# Natsuky.net
KiCad netlist of a schematic drawn in EAGLE
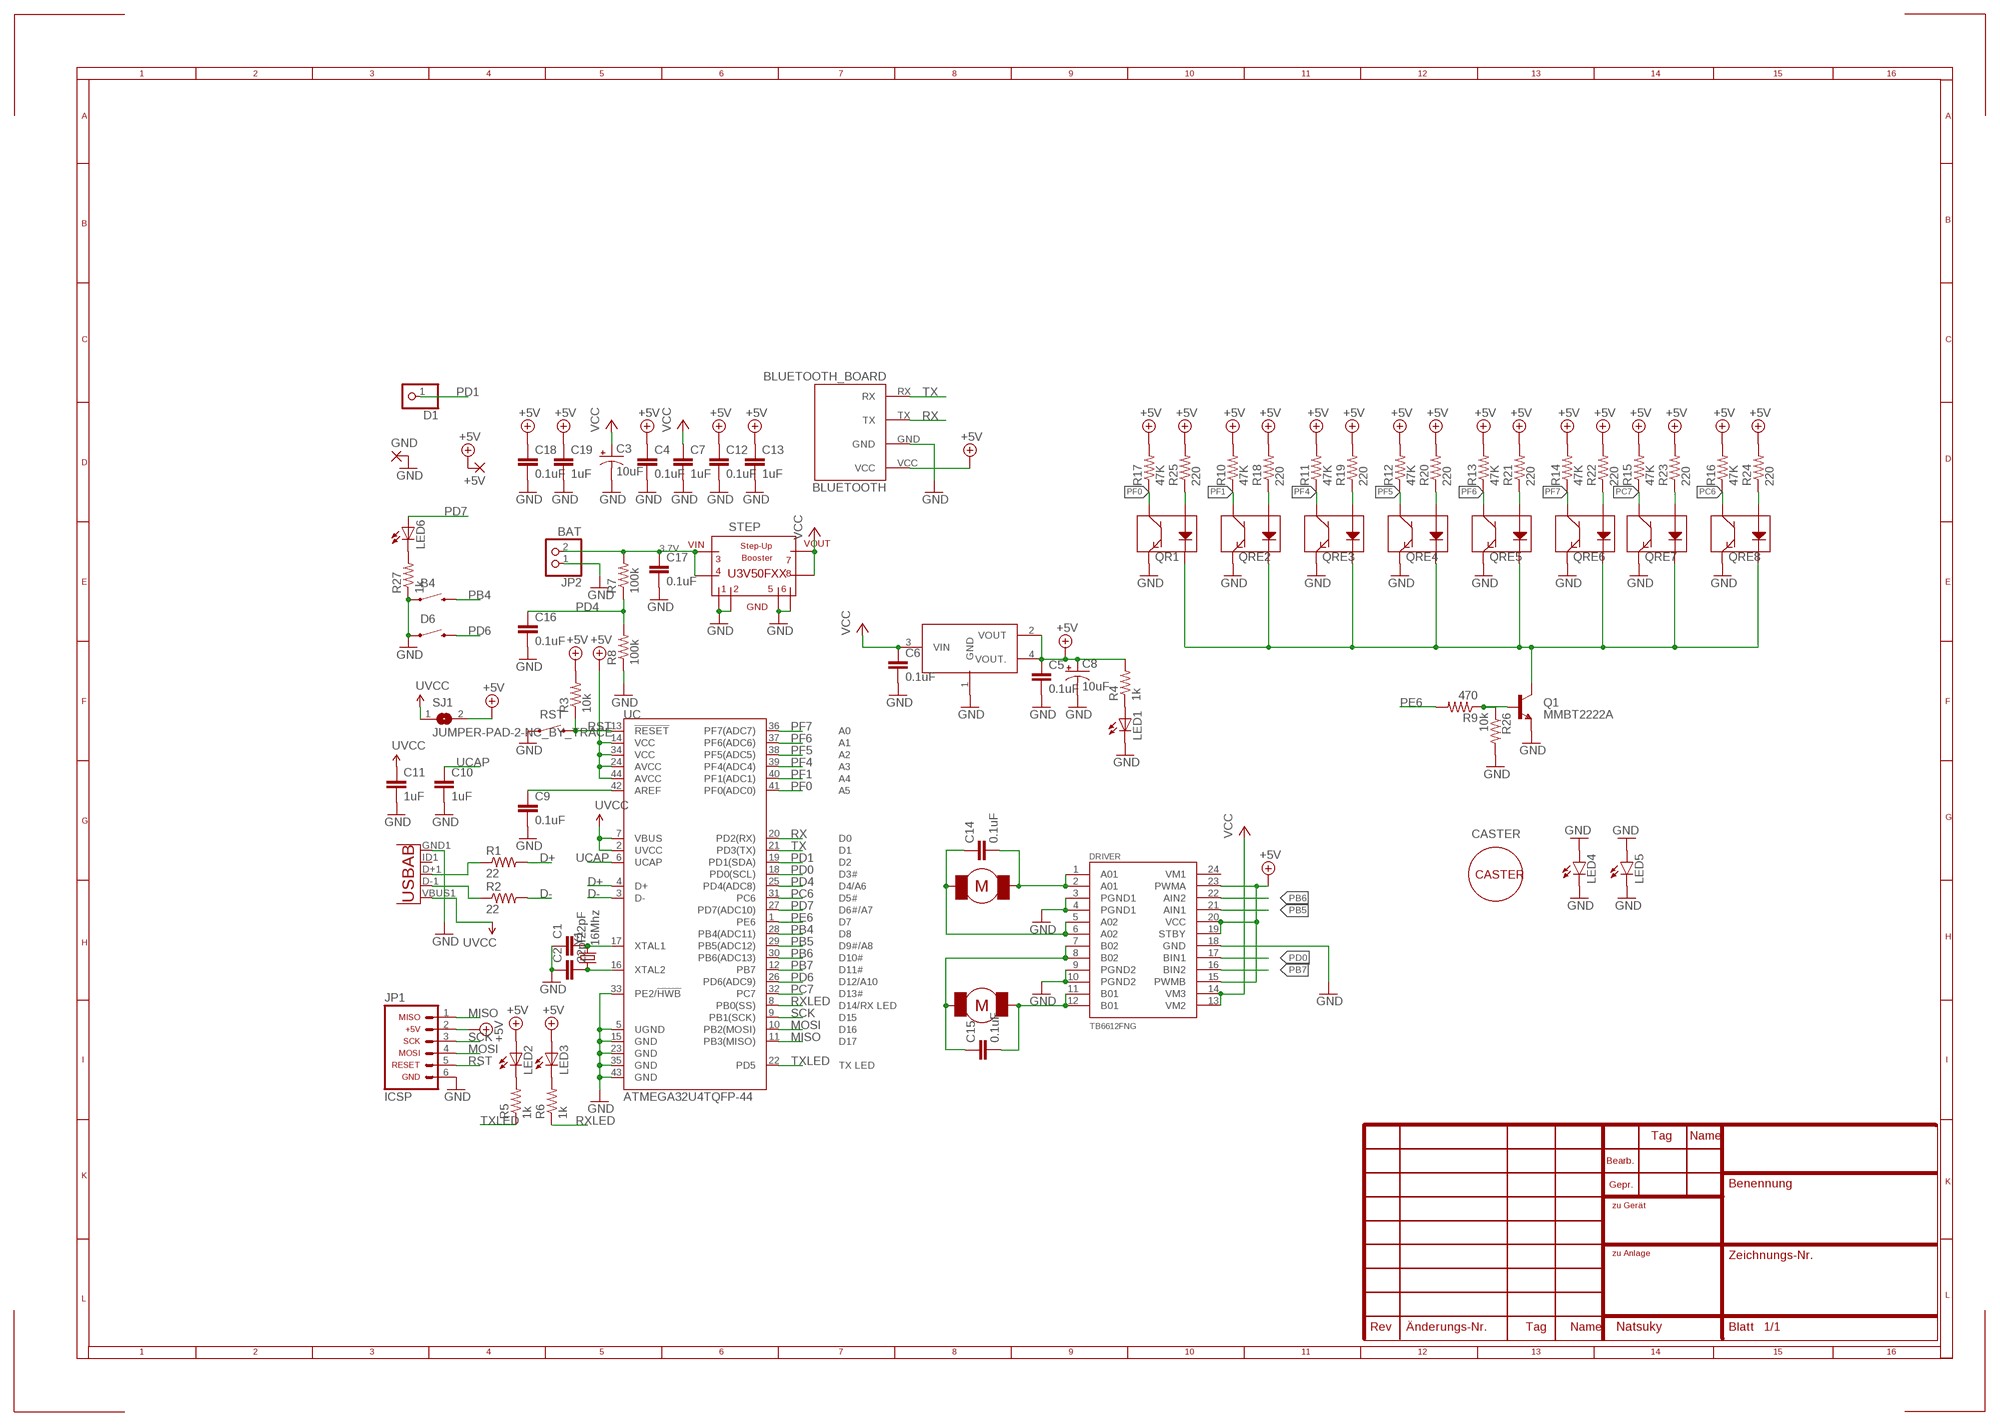
[diagram p0: schematic, sheet 1]

(export (version "E")
  (design (tool "Eeschema 10.0.6"))
  (components
    (comp (ref "+5V")
      (value "SMD2")
      (footprint "eagle-import:SMD1,27-2,54")
      (libsource (lib "eagle-import") (part "SMD2"))
    )
    (comp (ref "B4")
      (value "SWITCH-MOMENTARY-2SMD-1101NE")
      (footprint "eagle-import:TACTILE-SWITCH-1101NE")
      (libsource (lib "eagle-import") (part "SWITCH-MOMENTARY-2SMD-1101NE"))
    )
    (comp (ref "BLUETOOTH")
      (value "BLUETOOTH_BOARD")
      (footprint "eagle-import:BT_BOARD_FOOTPRINT")
      (libsource (lib "eagle-import") (part "BLUETOOTH_BOARD"))
    )
    (comp (ref "C1")
      (value "22pF")
      (footprint "eagle-import:0805")
      (libsource (lib "eagle-import") (part "CAP0805"))
    )
    (comp (ref "C2")
      (value "22pF")
      (footprint "eagle-import:0805")
      (libsource (lib "eagle-import") (part "CAP0805"))
    )
    (comp (ref "C3")
      (value "10uF")
      (footprint "eagle-import:EIA3216")
      (libsource (lib "eagle-import") (part "CAP_POL1206"))
    )
    (comp (ref "C4")
      (value "0.1uF")
      (footprint "eagle-import:0805")
      (libsource (lib "eagle-import") (part "SparkFun-Passives_CAP0805"))
    )
    (comp (ref "C5")
      (value "0.1uF")
      (footprint "eagle-import:0805")
      (libsource (lib "eagle-import") (part "SparkFun-Passives_CAP0805"))
    )
    (comp (ref "C6")
      (value "0.1uF")
      (footprint "eagle-import:0805")
      (libsource (lib "eagle-import") (part "SparkFun-Passives_CAP0805"))
    )
    (comp (ref "C7")
      (value "1uF")
      (footprint "eagle-import:0805")
      (libsource (lib "eagle-import") (part "SparkFun-Passives_CAP0805"))
    )
    (comp (ref "C8")
      (value "10uF")
      (footprint "eagle-import:PANASONIC_D")
      (libsource (lib "eagle-import") (part "CAP_POLD"))
    )
    (comp (ref "C9")
      (value "0.1uF")
      (footprint "eagle-import:0805")
      (libsource (lib "eagle-import") (part "SparkFun-Passives_CAP0805"))
    )
    (comp (ref "C10")
      (value "1uF")
      (footprint "eagle-import:0805")
      (libsource (lib "eagle-import") (part "SparkFun-Passives_CAP0805"))
    )
    (comp (ref "C11")
      (value "1uF")
      (footprint "eagle-import:0805")
      (libsource (lib "eagle-import") (part "SparkFun-Passives_CAP0805"))
    )
    (comp (ref "C12")
      (value "0.1uF")
      (footprint "eagle-import:0805")
      (libsource (lib "eagle-import") (part "SparkFun-Passives_CAP0805"))
    )
    (comp (ref "C13")
      (value "1uF")
      (footprint "eagle-import:0805")
      (libsource (lib "eagle-import") (part "SparkFun-Passives_CAP0805"))
    )
    (comp (ref "C14")
      (value "0.1uF")
      (footprint "eagle-import:0805")
      (libsource (lib "eagle-import") (part "SparkFun-Passives_CAP0805"))
    )
    (comp (ref "C15")
      (value "0.1uF")
      (footprint "eagle-import:0805")
      (libsource (lib "eagle-import") (part "SparkFun-Passives_CAP0805"))
    )
    (comp (ref "C16")
      (value "0.1uF")
      (footprint "eagle-import:0805")
      (libsource (lib "eagle-import") (part "SparkFun-Passives_CAP0805"))
    )
    (comp (ref "C17")
      (value "0.1uF")
      (footprint "eagle-import:0805")
      (libsource (lib "eagle-import") (part "SparkFun-Passives_CAP0805"))
    )
    (comp (ref "C18")
      (value "0.1uF")
      (footprint "eagle-import:0805")
      (libsource (lib "eagle-import") (part "SparkFun-Passives_CAP0805"))
    )
    (comp (ref "C19")
      (value "1uF")
      (footprint "eagle-import:0805")
      (libsource (lib "eagle-import") (part "SparkFun-Passives_CAP0805"))
    )
    (comp (ref "CASTER")
      (value "BALL_CASTER")
      (footprint "eagle-import:BALL_CASTER")
      (libsource (lib "eagle-import") (part "BALL_CASTER"))
    )
    (comp (ref "D1")
      (value "PINHD-1X1")
      (footprint "eagle-import:1X01")
      (libsource (lib "eagle-import") (part "PINHD-1X1"))
    )
    (comp (ref "D6")
      (value "SWITCH-MOMENTARY-2SMD-1101NE")
      (footprint "eagle-import:TACTILE-SWITCH-1101NE")
      (libsource (lib "eagle-import") (part "SWITCH-MOMENTARY-2SMD-1101NE"))
    )
    (comp (ref "DRIVER")
      (value "TB6612FNG")
      (footprint "eagle-import:SSOP24")
      (libsource (lib "eagle-import") (part "TB6612FNG"))
    )
    (comp (ref "GND")
      (value "SMD2")
      (footprint "eagle-import:SMD1,27-2,54")
      (libsource (lib "eagle-import") (part "SMD2"))
    )
    (comp (ref "JP1")
      (value "ICSP")
      (footprint "eagle-import:CONN-2X03")
      (libsource (lib "eagle-import") (part "ARDUINO_CONN-ICSP"))
    )
    (comp (ref "JP2")
      (value "BAT")
      (footprint "eagle-import:1X02")
      (libsource (lib "eagle-import") (part "PINHD-1X2"))
    )
    (comp (ref "LED1")
      (value "LEDCHIPLED_1206")
      (footprint "eagle-import:CHIPLED_1206")
      (libsource (lib "eagle-import") (part "LEDCHIPLED_1206"))
    )
    (comp (ref "LED2")
      (value "LEDCHIPLED_1206")
      (footprint "eagle-import:CHIPLED_1206")
      (libsource (lib "eagle-import") (part "LEDCHIPLED_1206"))
    )
    (comp (ref "LED3")
      (value "LEDCHIPLED_1206")
      (footprint "eagle-import:CHIPLED_1206")
      (libsource (lib "eagle-import") (part "LEDCHIPLED_1206"))
    )
    (comp (ref "LED4")
      (value "LED5MM")
      (footprint "eagle-import:LED5MM")
      (libsource (lib "eagle-import") (part "LED5MM"))
    )
    (comp (ref "LED5")
      (value "LED5MM")
      (footprint "eagle-import:LED5MM")
      (libsource (lib "eagle-import") (part "LED5MM"))
    )
    (comp (ref "LED6")
      (value "LEDCHIPLED_1206")
      (footprint "eagle-import:CHIPLED_1206")
      (libsource (lib "eagle-import") (part "LEDCHIPLED_1206"))
    )
    (comp (ref "M1")
      (value "BRACKET_EXTENDED_WHITE")
      (footprint "eagle-import:WHITE_EXT")
      (libsource (lib "eagle-import") (part "BRACKET_EXTENDED_WHITE"))
    )
    (comp (ref "M2")
      (value "BRACKET_EXTENDED_WHITE")
      (footprint "eagle-import:WHITE_EXT")
      (libsource (lib "eagle-import") (part "BRACKET_EXTENDED_WHITE"))
    )
    (comp (ref "Q1")
      (value "MMBT2222A")
      (footprint "eagle-import:SOT23-3")
      (libsource (lib "eagle-import") (part "TRANSISTOR_NPNMMBT2222A"))
    )
    (comp (ref "QR1")
      (value "QRE1113SMD-W")
      (footprint "eagle-import:QRE1113-W")
      (libsource (lib "eagle-import") (part "QRE1113SMD-W"))
    )
    (comp (ref "QRE2")
      (value "QRE1113SMD-W")
      (footprint "eagle-import:QRE1113-W")
      (libsource (lib "eagle-import") (part "QRE1113SMD-W"))
    )
    (comp (ref "QRE3")
      (value "QRE1113SMD-W")
      (footprint "eagle-import:QRE1113-W")
      (libsource (lib "eagle-import") (part "QRE1113SMD-W"))
    )
    (comp (ref "QRE4")
      (value "QRE1113SMD-W")
      (footprint "eagle-import:QRE1113-W")
      (libsource (lib "eagle-import") (part "QRE1113SMD-W"))
    )
    (comp (ref "QRE5")
      (value "QRE1113SMD-W")
      (footprint "eagle-import:QRE1113-W")
      (libsource (lib "eagle-import") (part "QRE1113SMD-W"))
    )
    (comp (ref "QRE6")
      (value "QRE1113SMD-W")
      (footprint "eagle-import:QRE1113-W")
      (libsource (lib "eagle-import") (part "QRE1113SMD-W"))
    )
    (comp (ref "QRE7")
      (value "QRE1113SMD-W")
      (footprint "eagle-import:QRE1113-W")
      (libsource (lib "eagle-import") (part "QRE1113SMD-W"))
    )
    (comp (ref "QRE8")
      (value "QRE1113SMD-W")
      (footprint "eagle-import:QRE1113-W")
      (libsource (lib "eagle-import") (part "QRE1113SMD-W"))
    )
    (comp (ref "R1")
      (value "22")
      (footprint "eagle-import:0805")
      (libsource (lib "eagle-import") (part "RESISTOR0805-RES"))
    )
    (comp (ref "R2")
      (value "22")
      (footprint "eagle-import:0805")
      (libsource (lib "eagle-import") (part "RESISTOR0805-RES"))
    )
    (comp (ref "R3")
      (value "10k")
      (footprint "eagle-import:0805")
      (libsource (lib "eagle-import") (part "RESISTOR0805-RES"))
    )
    (comp (ref "R4")
      (value "1k")
      (footprint "eagle-import:0805")
      (libsource (lib "eagle-import") (part "RESISTOR0805-RES"))
    )
    (comp (ref "R5")
      (value "1k")
      (footprint "eagle-import:0805")
      (libsource (lib "eagle-import") (part "RESISTOR0805-RES"))
    )
    (comp (ref "R6")
      (value "1k")
      (footprint "eagle-import:0805")
      (libsource (lib "eagle-import") (part "RESISTOR0805-RES"))
    )
    (comp (ref "R7")
      (value "100k")
      (footprint "eagle-import:0805")
      (libsource (lib "eagle-import") (part "RESISTOR0805-RES"))
    )
    (comp (ref "R8")
      (value "100k")
      (footprint "eagle-import:0805")
      (libsource (lib "eagle-import") (part "RESISTOR0805-RES"))
    )
    (comp (ref "R9")
      (value "470")
      (footprint "eagle-import:0805")
      (libsource (lib "eagle-import") (part "RESISTOR0805-RES"))
    )
    (comp (ref "R10")
      (value "47K")
      (footprint "eagle-import:0805")
      (libsource (lib "eagle-import") (part "RESISTOR0805-RES"))
    )
    (comp (ref "R11")
      (value "47K")
      (footprint "eagle-import:0805")
      (libsource (lib "eagle-import") (part "RESISTOR0805-RES"))
    )
    (comp (ref "R12")
      (value "47K")
      (footprint "eagle-import:0805")
      (libsource (lib "eagle-import") (part "RESISTOR0805-RES"))
    )
    (comp (ref "R13")
      (value "47K")
      (footprint "eagle-import:0805")
      (libsource (lib "eagle-import") (part "RESISTOR0805-RES"))
    )
    (comp (ref "R14")
      (value "47K")
      (footprint "eagle-import:0805")
      (libsource (lib "eagle-import") (part "RESISTOR0805-RES"))
    )
    (comp (ref "R15")
      (value "47K")
      (footprint "eagle-import:0805")
      (libsource (lib "eagle-import") (part "RESISTOR0805-RES"))
    )
    (comp (ref "R16")
      (value "47K")
      (footprint "eagle-import:0805")
      (libsource (lib "eagle-import") (part "RESISTOR0805-RES"))
    )
    (comp (ref "R17")
      (value "47K")
      (footprint "eagle-import:0805")
      (libsource (lib "eagle-import") (part "RESISTOR0805-RES"))
    )
    (comp (ref "R18")
      (value "220")
      (footprint "eagle-import:0805")
      (libsource (lib "eagle-import") (part "RESISTOR0805-RES"))
    )
    (comp (ref "R19")
      (value "220")
      (footprint "eagle-import:0805")
      (libsource (lib "eagle-import") (part "RESISTOR0805-RES"))
    )
    (comp (ref "R20")
      (value "220")
      (footprint "eagle-import:0805")
      (libsource (lib "eagle-import") (part "RESISTOR0805-RES"))
    )
    (comp (ref "R21")
      (value "220")
      (footprint "eagle-import:0805")
      (libsource (lib "eagle-import") (part "RESISTOR0805-RES"))
    )
    (comp (ref "R22")
      (value "220")
      (footprint "eagle-import:0805")
      (libsource (lib "eagle-import") (part "RESISTOR0805-RES"))
    )
    (comp (ref "R23")
      (value "220")
      (footprint "eagle-import:0805")
      (libsource (lib "eagle-import") (part "RESISTOR0805-RES"))
    )
    (comp (ref "R24")
      (value "220")
      (footprint "eagle-import:0805")
      (libsource (lib "eagle-import") (part "RESISTOR0805-RES"))
    )
    (comp (ref "R25")
      (value "220")
      (footprint "eagle-import:0805")
      (libsource (lib "eagle-import") (part "RESISTOR0805-RES"))
    )
    (comp (ref "R26")
      (value "10k")
      (footprint "eagle-import:0805")
      (libsource (lib "eagle-import") (part "RESISTOR0805-RES"))
    )
    (comp (ref "R27")
      (value "1k")
      (footprint "eagle-import:0805")
      (libsource (lib "eagle-import") (part "RESISTOR0805-RES"))
    )
    (comp (ref "REG")
      (value "LD1117S50TR")
      (footprint "eagle-import:SOT223")
      (libsource (lib "eagle-import") (part "LD1117S50TR"))
    )
    (comp (ref "RST")
      (value "SWITCH-MOMENTARY-2SMD-1101NE")
      (footprint "eagle-import:TACTILE-SWITCH-1101NE")
      (libsource (lib "eagle-import") (part "SWITCH-MOMENTARY-2SMD-1101NE"))
    )
    (comp (ref "SJ1")
      (value "JUMPER-PAD-2-NC_BY_TRACE")
      (footprint "eagle-import:SJ")
      (libsource (lib "eagle-import") (part "SJ"))
    )
    (comp (ref "STEP")
      (value "STEP-UP")
      (footprint "eagle-import:U3V50F12")
      (libsource (lib "eagle-import") (part "STEP-UP"))
    )
    (comp (ref "UC")
      (value "ATMEGA32U4TQFP-44")
      (footprint "eagle-import:TQFP44")
      (libsource (lib "eagle-import") (part "ATMEGA32U4TQFP-44"))
    )
    (comp (ref "X1")
      (value "usb")
      (footprint "eagle-import:USB-AB-MICRO-SMD-V03-IN&OUT")
      (libsource (lib "eagle-import") (part "USB-ABIN&OUT"))
    )
    (comp (ref "Y1")
      (value "16Mhz")
      (footprint "eagle-import:HC49US")
      (libsource (lib "eagle-import") (part "CRYSTALHC49US"))
    )
  )
  (nets
    (net (code "1") (name "+5V") (class "Default")
      (node (ref "+5V") (pin "1") (pinfunction "P_1") (pintype "passive"))
      (node (ref "BLUETOOTH") (pin "VCC") (pinfunction "VCC_VCC") (pintype "bidirectional"))
      (node (ref "C12") (pin "1") (pinfunction "1_1") (pintype "passive"))
      (node (ref "C13") (pin "1") (pinfunction "1_1") (pintype "passive"))
      (node (ref "C18") (pin "1") (pinfunction "1_1") (pintype "passive"))
      (node (ref "C19") (pin "1") (pinfunction "1_1") (pintype "passive"))
      (node (ref "C4") (pin "1") (pinfunction "1_1") (pintype "passive"))
      (node (ref "C5") (pin "1") (pinfunction "1_1") (pintype "passive"))
      (node (ref "C8") (pin "+") (pinfunction "+_+") (pintype "passive"))
      (node (ref "DRIVER") (pin "15") (pinfunction "PWMB_15") (pintype "bidirectional"))
      (node (ref "DRIVER") (pin "19") (pinfunction "STBY_19") (pintype "bidirectional"))
      (node (ref "DRIVER") (pin "20") (pinfunction "VCC_20") (pintype "bidirectional"))
      (node (ref "DRIVER") (pin "23") (pinfunction "PWMA_23") (pintype "bidirectional"))
      (node (ref "JP1") (pin "2") (pinfunction "2_2") (pintype "passive"))
      (node (ref "LED2") (pin "A") (pinfunction "A_A") (pintype "passive"))
      (node (ref "LED3") (pin "A") (pinfunction "A_A") (pintype "passive"))
      (node (ref "R10") (pin "2") (pinfunction "2_2") (pintype "passive"))
      (node (ref "R11") (pin "2") (pinfunction "2_2") (pintype "passive"))
      (node (ref "R12") (pin "2") (pinfunction "2_2") (pintype "passive"))
      (node (ref "R13") (pin "2") (pinfunction "2_2") (pintype "passive"))
      (node (ref "R14") (pin "2") (pinfunction "2_2") (pintype "passive"))
      (node (ref "R15") (pin "2") (pinfunction "2_2") (pintype "passive"))
      (node (ref "R16") (pin "2") (pinfunction "2_2") (pintype "passive"))
      (node (ref "R17") (pin "2") (pinfunction "2_2") (pintype "passive"))
      (node (ref "R18") (pin "2") (pinfunction "2_2") (pintype "passive"))
      (node (ref "R19") (pin "2") (pinfunction "2_2") (pintype "passive"))
      (node (ref "R20") (pin "2") (pinfunction "2_2") (pintype "passive"))
      (node (ref "R21") (pin "2") (pinfunction "2_2") (pintype "passive"))
      (node (ref "R22") (pin "2") (pinfunction "2_2") (pintype "passive"))
      (node (ref "R23") (pin "2") (pinfunction "2_2") (pintype "passive"))
      (node (ref "R24") (pin "2") (pinfunction "2_2") (pintype "passive"))
      (node (ref "R25") (pin "2") (pinfunction "2_2") (pintype "passive"))
      (node (ref "R3") (pin "2") (pinfunction "2_2") (pintype "passive"))
      (node (ref "R4") (pin "2") (pinfunction "2_2") (pintype "passive"))
      (node (ref "REG") (pin "2") (pinfunction "VOUT_2") (pintype "bidirectional"))
      (node (ref "REG") (pin "4") (pinfunction "VOUT._4") (pintype "bidirectional"))
      (node (ref "SJ1") (pin "2") (pinfunction "2_2") (pintype "passive"))
      (node (ref "UC") (pin "14") (pinfunction "VCC_14") (pintype "bidirectional"))
      (node (ref "UC") (pin "24") (pinfunction "AVCC_24") (pintype "bidirectional"))
      (node (ref "UC") (pin "34") (pinfunction "VCC_34") (pintype "bidirectional"))
      (node (ref "UC") (pin "44") (pinfunction "AVCC_44") (pintype "bidirectional"))
    )
    (net (code "2") (name "/3.7V") (class "Default")
      (node (ref "C17") (pin "1") (pinfunction "1_1") (pintype "passive"))
      (node (ref "JP2") (pin "2") (pinfunction "2_2") (pintype "passive"))
      (node (ref "R7") (pin "2") (pinfunction "2_2") (pintype "passive"))
      (node (ref "STEP") (pin "VIN") (pinfunction "VIN_VIN") (pintype "bidirectional"))
      (node (ref "STEP") (pin "VIN_4") (pinfunction "VIN4_VIN_4") (pintype "bidirectional"))
    )
    (net (code "3") (name "/D+") (class "Default")
      (node (ref "R1") (pin "2") (pinfunction "2_2") (pintype "passive"))
      (node (ref "UC") (pin "4") (pinfunction "D+_4") (pintype "bidirectional"))
    )
    (net (code "4") (name "/D-") (class "Default")
      (node (ref "R2") (pin "2") (pinfunction "2_2") (pintype "passive"))
      (node (ref "UC") (pin "3") (pinfunction "D-_3") (pintype "bidirectional"))
    )
    (net (code "5") (name "/MISO") (class "Default")
      (node (ref "JP1") (pin "1") (pinfunction "1_1") (pintype "passive"))
      (node (ref "UC") (pin "11") (pinfunction "PB3(MISO)_11") (pintype "bidirectional"))
    )
    (net (code "6") (name "/MOSI") (class "Default")
      (node (ref "JP1") (pin "4") (pinfunction "4_4") (pintype "passive"))
      (node (ref "UC") (pin "10") (pinfunction "PB2(MOSI)_10") (pintype "bidirectional"))
    )
    (net (code "7") (name "/PB4") (class "Default")
      (node (ref "B4") (pin "2") (pinfunction "2_2") (pintype "passive"))
      (node (ref "UC") (pin "28") (pinfunction "PB4(ADC11)_28") (pintype "bidirectional"))
    )
    (net (code "8") (name "/PD1") (class "Default")
      (node (ref "D1") (pin "1") (pinfunction "1_1") (pintype "passive"))
      (node (ref "UC") (pin "19") (pinfunction "PD1(SDA)_19") (pintype "bidirectional"))
    )
    (net (code "9") (name "/PD4") (class "Default")
      (node (ref "C16") (pin "1") (pinfunction "1_1") (pintype "passive"))
      (node (ref "R7") (pin "1") (pinfunction "1_1") (pintype "passive"))
      (node (ref "R8") (pin "2") (pinfunction "2_2") (pintype "passive"))
      (node (ref "UC") (pin "25") (pinfunction "PD4(ADC8)_25") (pintype "bidirectional"))
    )
    (net (code "10") (name "/PD6") (class "Default")
      (node (ref "D6") (pin "2") (pinfunction "2_2") (pintype "passive"))
      (node (ref "UC") (pin "26") (pinfunction "PD6(ADC9)_26") (pintype "bidirectional"))
    )
    (net (code "11") (name "/PD7") (class "Default")
      (node (ref "LED6") (pin "A") (pinfunction "A_A") (pintype "passive"))
      (node (ref "UC") (pin "27") (pinfunction "PD7(ADC10)_27") (pintype "bidirectional"))
    )
    (net (code "12") (name "/PE6") (class "Default")
      (node (ref "R9") (pin "2") (pinfunction "2_2") (pintype "passive"))
      (node (ref "UC") (pin "1") (pinfunction "PE6_1") (pintype "bidirectional"))
    )
    (net (code "13") (name "/RST") (class "Default")
      (node (ref "JP1") (pin "5") (pinfunction "5_5") (pintype "passive"))
      (node (ref "R3") (pin "1") (pinfunction "1_1") (pintype "passive"))
      (node (ref "RST") (pin "2") (pinfunction "2_2") (pintype "passive"))
      (node (ref "UC") (pin "13") (pinfunction "~{RESET}_13") (pintype "bidirectional"))
    )
    (net (code "14") (name "/RX") (class "Default")
      (node (ref "BLUETOOTH") (pin "TX") (pinfunction "TX_TX") (pintype "bidirectional"))
      (node (ref "UC") (pin "20") (pinfunction "PD2(RX)_20") (pintype "bidirectional"))
    )
    (net (code "15") (name "/RXLED") (class "Default")
      (node (ref "R6") (pin "1") (pinfunction "1_1") (pintype "passive"))
      (node (ref "UC") (pin "8") (pinfunction "PB0(SS)_8") (pintype "bidirectional"))
    )
    (net (code "16") (name "/SCK") (class "Default")
      (node (ref "JP1") (pin "3") (pinfunction "3_3") (pintype "passive"))
      (node (ref "UC") (pin "9") (pinfunction "PB1(SCK)_9") (pintype "bidirectional"))
    )
    (net (code "17") (name "/TX") (class "Default")
      (node (ref "BLUETOOTH") (pin "RX") (pinfunction "RX_RX") (pintype "bidirectional"))
      (node (ref "UC") (pin "21") (pinfunction "PD3(TX)_21") (pintype "bidirectional"))
    )
    (net (code "18") (name "/TXLED") (class "Default")
      (node (ref "R5") (pin "1") (pinfunction "1_1") (pintype "passive"))
      (node (ref "UC") (pin "22") (pinfunction "PD5_22") (pintype "bidirectional"))
    )
    (net (code "19") (name "/UCAP") (class "Default")
      (node (ref "C10") (pin "1") (pinfunction "1_1") (pintype "passive"))
      (node (ref "UC") (pin "6") (pinfunction "UCAP_6") (pintype "bidirectional"))
    )
    (net (code "20") (name "GND") (class "Default")
      (node (ref "B4") (pin "1") (pinfunction "1_1") (pintype "passive"))
      (node (ref "BLUETOOTH") (pin "GND") (pinfunction "GND_GND") (pintype "bidirectional"))
      (node (ref "C1") (pin "1") (pinfunction "1_1") (pintype "passive"))
      (node (ref "C10") (pin "2") (pinfunction "2_2") (pintype "passive"))
      (node (ref "C11") (pin "2") (pinfunction "2_2") (pintype "passive"))
      (node (ref "C12") (pin "2") (pinfunction "2_2") (pintype "passive"))
      (node (ref "C13") (pin "2") (pinfunction "2_2") (pintype "passive"))
      (node (ref "C16") (pin "2") (pinfunction "2_2") (pintype "passive"))
      (node (ref "C17") (pin "2") (pinfunction "2_2") (pintype "passive"))
      (node (ref "C18") (pin "2") (pinfunction "2_2") (pintype "passive"))
      (node (ref "C19") (pin "2") (pinfunction "2_2") (pintype "passive"))
      (node (ref "C2") (pin "1") (pinfunction "1_1") (pintype "passive"))
      (node (ref "C3") (pin "C") (pinfunction "-_C") (pintype "passive"))
      (node (ref "C4") (pin "2") (pinfunction "2_2") (pintype "passive"))
      (node (ref "C5") (pin "2") (pinfunction "2_2") (pintype "passive"))
      (node (ref "C6") (pin "2") (pinfunction "2_2") (pintype "passive"))
      (node (ref "C7") (pin "2") (pinfunction "2_2") (pintype "passive"))
      (node (ref "C8") (pin "-") (pinfunction "-_-") (pintype "passive"))
      (node (ref "C9") (pin "2") (pinfunction "2_2") (pintype "passive"))
      (node (ref "D6") (pin "1") (pinfunction "1_1") (pintype "passive"))
      (node (ref "DRIVER") (pin "10") (pinfunction "PGND2_10") (pintype "bidirectional"))
      (node (ref "DRIVER") (pin "18") (pinfunction "GND_18") (pintype "bidirectional"))
      (node (ref "DRIVER") (pin "3") (pinfunction "PGND1_3") (pintype "bidirectional"))
      (node (ref "DRIVER") (pin "4") (pinfunction "PGND1_4") (pintype "bidirectional"))
      (node (ref "DRIVER") (pin "9") (pinfunction "PGND2_9") (pintype "bidirectional"))
      (node (ref "GND") (pin "1") (pinfunction "P_1") (pintype "passive"))
      (node (ref "JP1") (pin "6") (pinfunction "6_6") (pintype "passive"))
      (node (ref "JP2") (pin "1") (pinfunction "1_1") (pintype "passive"))
      (node (ref "LED1") (pin "C") (pinfunction "C_C") (pintype "passive"))
      (node (ref "LED4") (pin "A") (pinfunction "A_A") (pintype "passive"))
      (node (ref "LED4") (pin "K") (pinfunction "C_K") (pintype "passive"))
      (node (ref "LED5") (pin "A") (pinfunction "A_A") (pintype "passive"))
      (node (ref "LED5") (pin "K") (pinfunction "C_K") (pintype "passive"))
      (node (ref "Q1") (pin "2") (pinfunction "E_2") (pintype "passive"))
      (node (ref "QR1") (pin "4") (pinfunction "E_4") (pintype "bidirectional"))
      (node (ref "QRE2") (pin "4") (pinfunction "E_4") (pintype "bidirectional"))
      (node (ref "QRE3") (pin "4") (pinfunction "E_4") (pintype "bidirectional"))
      (node (ref "QRE4") (pin "4") (pinfunction "E_4") (pintype "bidirectional"))
      (node (ref "QRE5") (pin "4") (pinfunction "E_4") (pintype "bidirectional"))
      (node (ref "QRE6") (pin "4") (pinfunction "E_4") (pintype "bidirectional"))
      (node (ref "QRE7") (pin "4") (pinfunction "E_4") (pintype "bidirectional"))
      (node (ref "QRE8") (pin "4") (pinfunction "E_4") (pintype "bidirectional"))
      (node (ref "R26") (pin "2") (pinfunction "2_2") (pintype "passive"))
      (node (ref "R27") (pin "1") (pinfunction "1_1") (pintype "passive"))
      (node (ref "R8") (pin "1") (pinfunction "1_1") (pintype "passive"))
      (node (ref "REG") (pin "1") (pinfunction "GND_1") (pintype "bidirectional"))
      (node (ref "RST") (pin "1") (pinfunction "1_1") (pintype "passive"))
      (node (ref "STEP") (pin "GND_OUT") (pinfunction "GND_VOUT_GND_OUT") (pintype "bidirectional"))
      (node (ref "STEP") (pin "GND_OUT_1") (pinfunction "GND_OUT1_GND_OUT_1") (pintype "bidirectional"))
      (node (ref "STEP") (pin "GND_VIN") (pinfunction "GND_VIN_GND_VIN") (pintype "bidirectional"))
      (node (ref "STEP") (pin "GND_VIN_1") (pinfunction "GND_VIN1_GND_VIN_1") (pintype "bidirectional"))
      (node (ref "UC") (pin "15") (pinfunction "GND_15") (pintype "bidirectional"))
      (node (ref "UC") (pin "23") (pinfunction "GND_23") (pintype "bidirectional"))
      (node (ref "UC") (pin "33") (pinfunction "PE2/~{HWB}_33") (pintype "bidirectional"))
      (node (ref "UC") (pin "35") (pinfunction "GND_35") (pintype "bidirectional"))
      (node (ref "UC") (pin "43") (pinfunction "GND_43") (pintype "bidirectional"))
      (node (ref "UC") (pin "5") (pinfunction "UGND_5") (pintype "bidirectional"))
      (node (ref "X1") (pin "GND1") (pinfunction "GND_GND1") (pintype "bidirectional"))
    )
    (net (code "21") (name "Net-(C14-Pad1)") (class "Default")
      (node (ref "C14") (pin "1") (pinfunction "1_1") (pintype "passive"))
      (node (ref "DRIVER") (pin "5") (pinfunction "A02_5") (pintype "bidirectional"))
      (node (ref "DRIVER") (pin "6") (pinfunction "A02_6") (pintype "bidirectional"))
      (node (ref "M2") (pin "M2") (pinfunction "M2_M2") (pintype "bidirectional"))
    )
    (net (code "22") (name "Net-(C14-Pad2)") (class "Default")
      (node (ref "C14") (pin "2") (pinfunction "2_2") (pintype "passive"))
      (node (ref "DRIVER") (pin "1") (pinfunction "A01_1") (pintype "bidirectional"))
      (node (ref "DRIVER") (pin "2") (pinfunction "A01_2") (pintype "bidirectional"))
      (node (ref "M2") (pin "M1") (pinfunction "M1_M1") (pintype "bidirectional"))
    )
    (net (code "23") (name "Net-(C15-Pad1)") (class "Default")
      (node (ref "C15") (pin "1") (pinfunction "1_1") (pintype "passive"))
      (node (ref "DRIVER") (pin "7") (pinfunction "B02_7") (pintype "bidirectional"))
      (node (ref "DRIVER") (pin "8") (pinfunction "B02_8") (pintype "bidirectional"))
      (node (ref "M1") (pin "M1") (pinfunction "M1_M1") (pintype "bidirectional"))
    )
    (net (code "24") (name "Net-(C15-Pad2)") (class "Default")
      (node (ref "C15") (pin "2") (pinfunction "2_2") (pintype "passive"))
      (node (ref "DRIVER") (pin "11") (pinfunction "B01_11") (pintype "bidirectional"))
      (node (ref "DRIVER") (pin "12") (pinfunction "B01_12") (pintype "bidirectional"))
      (node (ref "M1") (pin "M2") (pinfunction "M2_M2") (pintype "bidirectional"))
    )
    (net (code "25") (name "Net-(LED1-PadA)") (class "Default")
      (node (ref "LED1") (pin "A") (pinfunction "A_A") (pintype "passive"))
      (node (ref "R4") (pin "1") (pinfunction "1_1") (pintype "passive"))
    )
    (net (code "26") (name "Net-(LED2-PadC)") (class "Default")
      (node (ref "LED2") (pin "C") (pinfunction "C_C") (pintype "passive"))
      (node (ref "R5") (pin "2") (pinfunction "2_2") (pintype "passive"))
    )
    (net (code "27") (name "Net-(LED3-PadC)") (class "Default")
      (node (ref "LED3") (pin "C") (pinfunction "C_C") (pintype "passive"))
      (node (ref "R6") (pin "2") (pinfunction "2_2") (pintype "passive"))
    )
    (net (code "28") (name "Net-(LED6-PadC)") (class "Default")
      (node (ref "LED6") (pin "C") (pinfunction "C_C") (pintype "passive"))
      (node (ref "R27") (pin "2") (pinfunction "2_2") (pintype "passive"))
    )
    (net (code "29") (name "Net-(Q1-B)") (class "Default")
      (node (ref "Q1") (pin "1") (pinfunction "B_1") (pintype "passive"))
      (node (ref "R26") (pin "1") (pinfunction "1_1") (pintype "passive"))
      (node (ref "R9") (pin "1") (pinfunction "1_1") (pintype "passive"))
    )
    (net (code "30") (name "Net-(Q1-C)") (class "Default")
      (node (ref "Q1") (pin "3") (pinfunction "C_3") (pintype "passive"))
      (node (ref "QR1") (pin "2") (pinfunction "K_2") (pintype "bidirectional"))
      (node (ref "QRE2") (pin "2") (pinfunction "K_2") (pintype "bidirectional"))
      (node (ref "QRE3") (pin "2") (pinfunction "K_2") (pintype "bidirectional"))
      (node (ref "QRE4") (pin "2") (pinfunction "K_2") (pintype "bidirectional"))
      (node (ref "QRE5") (pin "2") (pinfunction "K_2") (pintype "bidirectional"))
      (node (ref "QRE6") (pin "2") (pinfunction "K_2") (pintype "bidirectional"))
      (node (ref "QRE7") (pin "2") (pinfunction "K_2") (pintype "bidirectional"))
      (node (ref "QRE8") (pin "2") (pinfunction "K_2") (pintype "bidirectional"))
    )
    (net (code "31") (name "Net-(QR1-A)") (class "Default")
      (node (ref "QR1") (pin "1") (pinfunction "A_1") (pintype "bidirectional"))
      (node (ref "R25") (pin "1") (pinfunction "1_1") (pintype "passive"))
    )
    (net (code "32") (name "Net-(QRE2-A)") (class "Default")
      (node (ref "QRE2") (pin "1") (pinfunction "A_1") (pintype "bidirectional"))
      (node (ref "R18") (pin "1") (pinfunction "1_1") (pintype "passive"))
    )
    (net (code "33") (name "Net-(QRE3-A)") (class "Default")
      (node (ref "QRE3") (pin "1") (pinfunction "A_1") (pintype "bidirectional"))
      (node (ref "R19") (pin "1") (pinfunction "1_1") (pintype "passive"))
    )
    (net (code "34") (name "Net-(QRE4-A)") (class "Default")
      (node (ref "QRE4") (pin "1") (pinfunction "A_1") (pintype "bidirectional"))
      (node (ref "R20") (pin "1") (pinfunction "1_1") (pintype "passive"))
    )
    (net (code "35") (name "Net-(QRE5-A)") (class "Default")
      (node (ref "QRE5") (pin "1") (pinfunction "A_1") (pintype "bidirectional"))
      (node (ref "R21") (pin "1") (pinfunction "1_1") (pintype "passive"))
    )
    (net (code "36") (name "Net-(QRE6-A)") (class "Default")
      (node (ref "QRE6") (pin "1") (pinfunction "A_1") (pintype "bidirectional"))
      (node (ref "R22") (pin "1") (pinfunction "1_1") (pintype "passive"))
    )
    (net (code "37") (name "Net-(QRE7-A)") (class "Default")
      (node (ref "QRE7") (pin "1") (pinfunction "A_1") (pintype "bidirectional"))
      (node (ref "R23") (pin "1") (pinfunction "1_1") (pintype "passive"))
    )
    (net (code "38") (name "Net-(QRE8-A)") (class "Default")
      (node (ref "QRE8") (pin "1") (pinfunction "A_1") (pintype "bidirectional"))
      (node (ref "R24") (pin "1") (pinfunction "1_1") (pintype "passive"))
    )
    (net (code "39") (name "Net-(UC-AREF)") (class "Default")
      (node (ref "C9") (pin "1") (pinfunction "1_1") (pintype "passive"))
      (node (ref "UC") (pin "42") (pinfunction "AREF_42") (pintype "bidirectional"))
    )
    (net (code "40") (name "Net-(UC-XTAL1)") (class "Default")
      (node (ref "C1") (pin "2") (pinfunction "2_2") (pintype "passive"))
      (node (ref "UC") (pin "17") (pinfunction "XTAL1_17") (pintype "bidirectional"))
      (node (ref "Y1") (pin "2") (pinfunction "2_2") (pintype "passive"))
    )
    (net (code "41") (name "Net-(UC-XTAL2)") (class "Default")
      (node (ref "C2") (pin "2") (pinfunction "2_2") (pintype "passive"))
      (node (ref "UC") (pin "16") (pinfunction "XTAL2_16") (pintype "bidirectional"))
      (node (ref "Y1") (pin "1") (pinfunction "1_1") (pintype "passive"))
    )
    (net (code "42") (name "Net-(X1-D+)") (class "Default")
      (node (ref "R1") (pin "1") (pinfunction "1_1") (pintype "passive"))
      (node (ref "X1") (pin "D+1") (pinfunction "D+_D+1") (pintype "bidirectional"))
    )
    (net (code "43") (name "Net-(X1-D-)") (class "Default")
      (node (ref "R2") (pin "1") (pinfunction "1_1") (pintype "passive"))
      (node (ref "X1") (pin "D-1") (pinfunction "D-_D-1") (pintype "bidirectional"))
    )
    (net (code "44") (name "PB5") (class "Default")
      (node (ref "DRIVER") (pin "21") (pinfunction "AIN1_21") (pintype "bidirectional"))
      (node (ref "UC") (pin "29") (pinfunction "PB5(ADC12)_29") (pintype "bidirectional"))
    )
    (net (code "45") (name "PB6") (class "Default")
      (node (ref "DRIVER") (pin "22") (pinfunction "AIN2_22") (pintype "bidirectional"))
      (node (ref "UC") (pin "30") (pinfunction "PB6(ADC13)_30") (pintype "bidirectional"))
    )
    (net (code "46") (name "PB7") (class "Default")
      (node (ref "DRIVER") (pin "16") (pinfunction "BIN2_16") (pintype "bidirectional"))
      (node (ref "UC") (pin "12") (pinfunction "PB7_12") (pintype "bidirectional"))
    )
    (net (code "47") (name "PC6") (class "Default")
      (node (ref "QRE8") (pin "3") (pinfunction "C_3") (pintype "bidirectional"))
      (node (ref "R16") (pin "1") (pinfunction "1_1") (pintype "passive"))
      (node (ref "UC") (pin "31") (pinfunction "PC6_31") (pintype "bidirectional"))
    )
    (net (code "48") (name "PC7") (class "Default")
      (node (ref "QRE7") (pin "3") (pinfunction "C_3") (pintype "bidirectional"))
      (node (ref "R15") (pin "1") (pinfunction "1_1") (pintype "passive"))
      (node (ref "UC") (pin "32") (pinfunction "PC7_32") (pintype "bidirectional"))
    )
    (net (code "49") (name "PD0") (class "Default")
      (node (ref "DRIVER") (pin "17") (pinfunction "BIN1_17") (pintype "bidirectional"))
      (node (ref "UC") (pin "18") (pinfunction "PD0(SCL)_18") (pintype "bidirectional"))
    )
    (net (code "50") (name "PF0") (class "Default")
      (node (ref "QR1") (pin "3") (pinfunction "C_3") (pintype "bidirectional"))
      (node (ref "R17") (pin "1") (pinfunction "1_1") (pintype "passive"))
      (node (ref "UC") (pin "41") (pinfunction "PF0(ADC0)_41") (pintype "bidirectional"))
    )
    (net (code "51") (name "PF1") (class "Default")
      (node (ref "QRE2") (pin "3") (pinfunction "C_3") (pintype "bidirectional"))
      (node (ref "R10") (pin "1") (pinfunction "1_1") (pintype "passive"))
      (node (ref "UC") (pin "40") (pinfunction "PF1(ADC1)_40") (pintype "bidirectional"))
    )
    (net (code "52") (name "PF4") (class "Default")
      (node (ref "QRE3") (pin "3") (pinfunction "C_3") (pintype "bidirectional"))
      (node (ref "R11") (pin "1") (pinfunction "1_1") (pintype "passive"))
      (node (ref "UC") (pin "39") (pinfunction "PF4(ADC4)_39") (pintype "bidirectional"))
    )
    (net (code "53") (name "PF5") (class "Default")
      (node (ref "QRE4") (pin "3") (pinfunction "C_3") (pintype "bidirectional"))
      (node (ref "R12") (pin "1") (pinfunction "1_1") (pintype "passive"))
      (node (ref "UC") (pin "38") (pinfunction "PF5(ADC5)_38") (pintype "bidirectional"))
    )
    (net (code "54") (name "PF6") (class "Default")
      (node (ref "QRE5") (pin "3") (pinfunction "C_3") (pintype "bidirectional"))
      (node (ref "R13") (pin "1") (pinfunction "1_1") (pintype "passive"))
      (node (ref "UC") (pin "37") (pinfunction "PF6(ADC6)_37") (pintype "bidirectional"))
    )
    (net (code "55") (name "PF7") (class "Default")
      (node (ref "QRE6") (pin "3") (pinfunction "C_3") (pintype "bidirectional"))
      (node (ref "R14") (pin "1") (pinfunction "1_1") (pintype "passive"))
      (node (ref "UC") (pin "36") (pinfunction "PF7(ADC7)_36") (pintype "bidirectional"))
    )
    (net (code "56") (name "UVCC") (class "Default")
      (node (ref "C11") (pin "1") (pinfunction "1_1") (pintype "passive"))
      (node (ref "SJ1") (pin "1") (pinfunction "1_1") (pintype "passive"))
      (node (ref "UC") (pin "2") (pinfunction "UVCC_2") (pintype "bidirectional"))
      (node (ref "UC") (pin "7") (pinfunction "VBUS_7") (pintype "bidirectional"))
      (node (ref "X1") (pin "VBUS1") (pinfunction "VBUS_VBUS1") (pintype "bidirectional"))
    )
    (net (code "57") (name "VCC") (class "Default")
      (node (ref "C3") (pin "A") (pinfunction "+_A") (pintype "passive"))
      (node (ref "C6") (pin "1") (pinfunction "1_1") (pintype "passive"))
      (node (ref "C7") (pin "1") (pinfunction "1_1") (pintype "passive"))
      (node (ref "DRIVER") (pin "13") (pinfunction "VM2_13") (pintype "bidirectional"))
      (node (ref "DRIVER") (pin "14") (pinfunction "VM3_14") (pintype "bidirectional"))
      (node (ref "REG") (pin "3") (pinfunction "VIN_3") (pintype "bidirectional"))
      (node (ref "STEP") (pin "VOUT") (pinfunction "VOUT_VOUT") (pintype "bidirectional"))
      (node (ref "STEP") (pin "VOUT_4") (pinfunction "VOUT4_VOUT_4") (pintype "bidirectional"))
    )
    (net (code "58") (name "unconnected-(DRIVER-VM1-Pad24)") (class "Default")
      (node (ref "DRIVER") (pin "24") (pinfunction "VM1_24") (pintype "bidirectional"))
    )
    (net (code "59") (name "unconnected-(X1-USBID-PadID1)") (class "Default")
      (node (ref "X1") (pin "ID1") (pinfunction "USBID_ID1") (pintype "bidirectional"))
    )
  )
)
